# Layout.net
KiCad netlist of a schematic drawn in EasyEDA
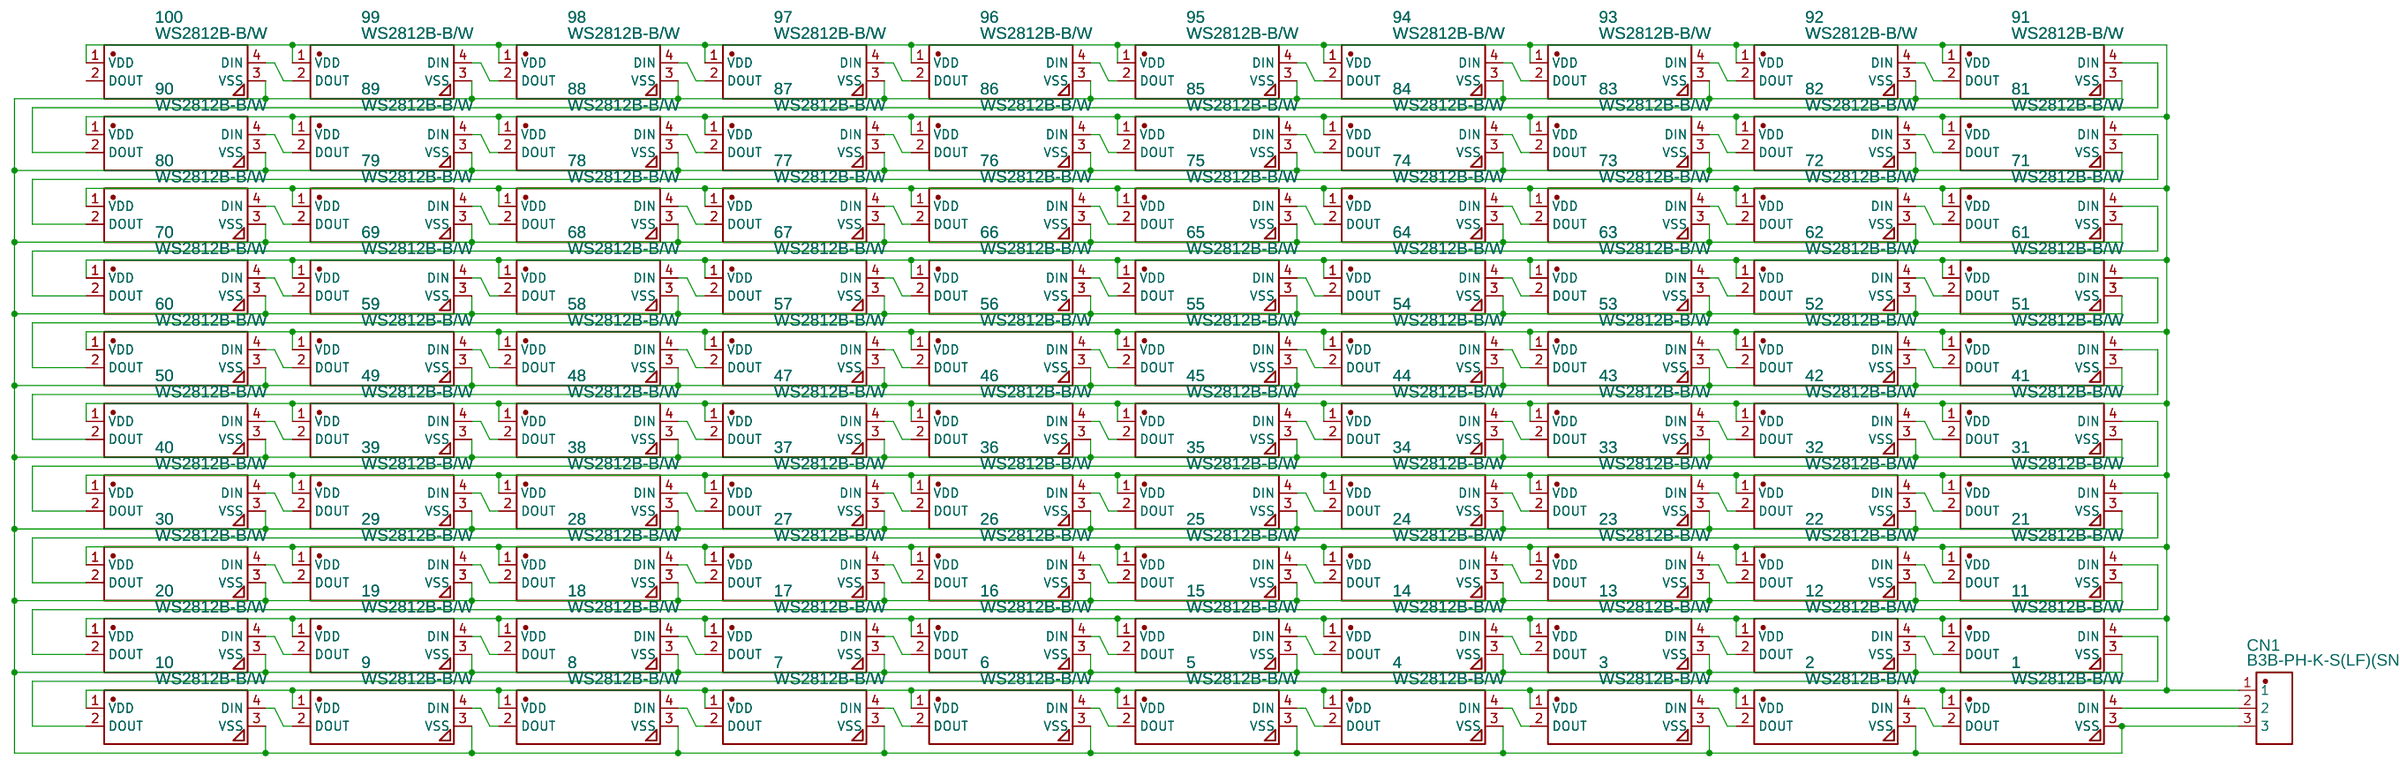
[diagram p0: schematic sheet]

(export (version "E")
  (design (tool "Eeschema 10.0.6"))
  (components
    (comp (ref "1")
      (value "WS2812B-B/W")
      (fields (field (name "Manufacturer Part") "WS2812B-B/T") (field (name "Manufacturer") "worldsemi"))
      (libsource (lib "") (part "WS2812B-B/W"))
    )
    (comp (ref "2")
      (value "WS2812B-B/W")
      (fields (field (name "Manufacturer Part") "WS2812B-B/T") (field (name "Manufacturer") "worldsemi"))
      (libsource (lib "") (part "WS2812B-B/W"))
    )
    (comp (ref "3")
      (value "WS2812B-B/W")
      (fields (field (name "Manufacturer Part") "WS2812B-B/T") (field (name "Manufacturer") "worldsemi"))
      (libsource (lib "") (part "WS2812B-B/W"))
    )
    (comp (ref "4")
      (value "WS2812B-B/W")
      (fields (field (name "Manufacturer Part") "WS2812B-B/T") (field (name "Manufacturer") "worldsemi"))
      (libsource (lib "") (part "WS2812B-B/W"))
    )
    (comp (ref "5")
      (value "WS2812B-B/W")
      (fields (field (name "Manufacturer Part") "WS2812B-B/T") (field (name "Manufacturer") "worldsemi"))
      (libsource (lib "") (part "WS2812B-B/W"))
    )
    (comp (ref "6")
      (value "WS2812B-B/W")
      (fields (field (name "Manufacturer Part") "WS2812B-B/T") (field (name "Manufacturer") "worldsemi"))
      (libsource (lib "") (part "WS2812B-B/W"))
    )
    (comp (ref "7")
      (value "WS2812B-B/W")
      (fields (field (name "Manufacturer Part") "WS2812B-B/T") (field (name "Manufacturer") "worldsemi"))
      (libsource (lib "") (part "WS2812B-B/W"))
    )
    (comp (ref "8")
      (value "WS2812B-B/W")
      (fields (field (name "Manufacturer Part") "WS2812B-B/T") (field (name "Manufacturer") "worldsemi"))
      (libsource (lib "") (part "WS2812B-B/W"))
    )
    (comp (ref "9")
      (value "WS2812B-B/W")
      (fields (field (name "Manufacturer Part") "WS2812B-B/T") (field (name "Manufacturer") "worldsemi"))
      (libsource (lib "") (part "WS2812B-B/W"))
    )
    (comp (ref "10")
      (value "WS2812B-B/W")
      (fields (field (name "Manufacturer Part") "WS2812B-B/T") (field (name "Manufacturer") "worldsemi"))
      (libsource (lib "") (part "WS2812B-B/W"))
    )
    (comp (ref "11")
      (value "WS2812B-B/W")
      (fields (field (name "Manufacturer Part") "WS2812B-B/T") (field (name "Manufacturer") "worldsemi"))
      (libsource (lib "") (part "WS2812B-B/W"))
    )
    (comp (ref "12")
      (value "WS2812B-B/W")
      (fields (field (name "Manufacturer Part") "WS2812B-B/T") (field (name "Manufacturer") "worldsemi"))
      (libsource (lib "") (part "WS2812B-B/W"))
    )
    (comp (ref "13")
      (value "WS2812B-B/W")
      (fields (field (name "Manufacturer Part") "WS2812B-B/T") (field (name "Manufacturer") "worldsemi"))
      (libsource (lib "") (part "WS2812B-B/W"))
    )
    (comp (ref "14")
      (value "WS2812B-B/W")
      (fields (field (name "Manufacturer Part") "WS2812B-B/T") (field (name "Manufacturer") "worldsemi"))
      (libsource (lib "") (part "WS2812B-B/W"))
    )
    (comp (ref "15")
      (value "WS2812B-B/W")
      (fields (field (name "Manufacturer Part") "WS2812B-B/T") (field (name "Manufacturer") "worldsemi"))
      (libsource (lib "") (part "WS2812B-B/W"))
    )
    (comp (ref "16")
      (value "WS2812B-B/W")
      (fields (field (name "Manufacturer Part") "WS2812B-B/T") (field (name "Manufacturer") "worldsemi"))
      (libsource (lib "") (part "WS2812B-B/W"))
    )
    (comp (ref "17")
      (value "WS2812B-B/W")
      (fields (field (name "Manufacturer Part") "WS2812B-B/T") (field (name "Manufacturer") "worldsemi"))
      (libsource (lib "") (part "WS2812B-B/W"))
    )
    (comp (ref "18")
      (value "WS2812B-B/W")
      (fields (field (name "Manufacturer Part") "WS2812B-B/T") (field (name "Manufacturer") "worldsemi"))
      (libsource (lib "") (part "WS2812B-B/W"))
    )
    (comp (ref "19")
      (value "WS2812B-B/W")
      (fields (field (name "Manufacturer Part") "WS2812B-B/T") (field (name "Manufacturer") "worldsemi"))
      (libsource (lib "") (part "WS2812B-B/W"))
    )
    (comp (ref "20")
      (value "WS2812B-B/W")
      (fields (field (name "Manufacturer Part") "WS2812B-B/T") (field (name "Manufacturer") "worldsemi"))
      (libsource (lib "") (part "WS2812B-B/W"))
    )
    (comp (ref "21")
      (value "WS2812B-B/W")
      (fields (field (name "Manufacturer Part") "WS2812B-B/T") (field (name "Manufacturer") "worldsemi"))
      (libsource (lib "") (part "WS2812B-B/W"))
    )
    (comp (ref "22")
      (value "WS2812B-B/W")
      (fields (field (name "Manufacturer Part") "WS2812B-B/T") (field (name "Manufacturer") "worldsemi"))
      (libsource (lib "") (part "WS2812B-B/W"))
    )
    (comp (ref "23")
      (value "WS2812B-B/W")
      (fields (field (name "Manufacturer Part") "WS2812B-B/T") (field (name "Manufacturer") "worldsemi"))
      (libsource (lib "") (part "WS2812B-B/W"))
    )
    (comp (ref "24")
      (value "WS2812B-B/W")
      (fields (field (name "Manufacturer Part") "WS2812B-B/T") (field (name "Manufacturer") "worldsemi"))
      (libsource (lib "") (part "WS2812B-B/W"))
    )
    (comp (ref "25")
      (value "WS2812B-B/W")
      (fields (field (name "Manufacturer Part") "WS2812B-B/T") (field (name "Manufacturer") "worldsemi"))
      (libsource (lib "") (part "WS2812B-B/W"))
    )
    (comp (ref "26")
      (value "WS2812B-B/W")
      (fields (field (name "Manufacturer Part") "WS2812B-B/T") (field (name "Manufacturer") "worldsemi"))
      (libsource (lib "") (part "WS2812B-B/W"))
    )
    (comp (ref "27")
      (value "WS2812B-B/W")
      (fields (field (name "Manufacturer Part") "WS2812B-B/T") (field (name "Manufacturer") "worldsemi"))
      (libsource (lib "") (part "WS2812B-B/W"))
    )
    (comp (ref "28")
      (value "WS2812B-B/W")
      (fields (field (name "Manufacturer Part") "WS2812B-B/T") (field (name "Manufacturer") "worldsemi"))
      (libsource (lib "") (part "WS2812B-B/W"))
    )
    (comp (ref "29")
      (value "WS2812B-B/W")
      (fields (field (name "Manufacturer Part") "WS2812B-B/T") (field (name "Manufacturer") "worldsemi"))
      (libsource (lib "") (part "WS2812B-B/W"))
    )
    (comp (ref "30")
      (value "WS2812B-B/W")
      (fields (field (name "Manufacturer Part") "WS2812B-B/T") (field (name "Manufacturer") "worldsemi"))
      (libsource (lib "") (part "WS2812B-B/W"))
    )
    (comp (ref "31")
      (value "WS2812B-B/W")
      (fields (field (name "Manufacturer Part") "WS2812B-B/T") (field (name "Manufacturer") "worldsemi"))
      (libsource (lib "") (part "WS2812B-B/W"))
    )
    (comp (ref "32")
      (value "WS2812B-B/W")
      (fields (field (name "Manufacturer Part") "WS2812B-B/T") (field (name "Manufacturer") "worldsemi"))
      (libsource (lib "") (part "WS2812B-B/W"))
    )
    (comp (ref "33")
      (value "WS2812B-B/W")
      (fields (field (name "Manufacturer Part") "WS2812B-B/T") (field (name "Manufacturer") "worldsemi"))
      (libsource (lib "") (part "WS2812B-B/W"))
    )
    (comp (ref "34")
      (value "WS2812B-B/W")
      (fields (field (name "Manufacturer Part") "WS2812B-B/T") (field (name "Manufacturer") "worldsemi"))
      (libsource (lib "") (part "WS2812B-B/W"))
    )
    (comp (ref "35")
      (value "WS2812B-B/W")
      (fields (field (name "Manufacturer Part") "WS2812B-B/T") (field (name "Manufacturer") "worldsemi"))
      (libsource (lib "") (part "WS2812B-B/W"))
    )
    (comp (ref "36")
      (value "WS2812B-B/W")
      (fields (field (name "Manufacturer Part") "WS2812B-B/T") (field (name "Manufacturer") "worldsemi"))
      (libsource (lib "") (part "WS2812B-B/W"))
    )
    (comp (ref "37")
      (value "WS2812B-B/W")
      (fields (field (name "Manufacturer Part") "WS2812B-B/T") (field (name "Manufacturer") "worldsemi"))
      (libsource (lib "") (part "WS2812B-B/W"))
    )
    (comp (ref "38")
      (value "WS2812B-B/W")
      (fields (field (name "Manufacturer Part") "WS2812B-B/T") (field (name "Manufacturer") "worldsemi"))
      (libsource (lib "") (part "WS2812B-B/W"))
    )
    (comp (ref "39")
      (value "WS2812B-B/W")
      (fields (field (name "Manufacturer Part") "WS2812B-B/T") (field (name "Manufacturer") "worldsemi"))
      (libsource (lib "") (part "WS2812B-B/W"))
    )
    (comp (ref "40")
      (value "WS2812B-B/W")
      (fields (field (name "Manufacturer Part") "WS2812B-B/T") (field (name "Manufacturer") "worldsemi"))
      (libsource (lib "") (part "WS2812B-B/W"))
    )
    (comp (ref "41")
      (value "WS2812B-B/W")
      (fields (field (name "Manufacturer Part") "WS2812B-B/T") (field (name "Manufacturer") "worldsemi"))
      (libsource (lib "") (part "WS2812B-B/W"))
    )
    (comp (ref "42")
      (value "WS2812B-B/W")
      (fields (field (name "Manufacturer Part") "WS2812B-B/T") (field (name "Manufacturer") "worldsemi"))
      (libsource (lib "") (part "WS2812B-B/W"))
    )
    (comp (ref "43")
      (value "WS2812B-B/W")
      (fields (field (name "Manufacturer Part") "WS2812B-B/T") (field (name "Manufacturer") "worldsemi"))
      (libsource (lib "") (part "WS2812B-B/W"))
    )
    (comp (ref "44")
      (value "WS2812B-B/W")
      (fields (field (name "Manufacturer Part") "WS2812B-B/T") (field (name "Manufacturer") "worldsemi"))
      (libsource (lib "") (part "WS2812B-B/W"))
    )
    (comp (ref "45")
      (value "WS2812B-B/W")
      (fields (field (name "Manufacturer Part") "WS2812B-B/T") (field (name "Manufacturer") "worldsemi"))
      (libsource (lib "") (part "WS2812B-B/W"))
    )
    (comp (ref "46")
      (value "WS2812B-B/W")
      (fields (field (name "Manufacturer Part") "WS2812B-B/T") (field (name "Manufacturer") "worldsemi"))
      (libsource (lib "") (part "WS2812B-B/W"))
    )
    (comp (ref "47")
      (value "WS2812B-B/W")
      (fields (field (name "Manufacturer Part") "WS2812B-B/T") (field (name "Manufacturer") "worldsemi"))
      (libsource (lib "") (part "WS2812B-B/W"))
    )
    (comp (ref "48")
      (value "WS2812B-B/W")
      (fields (field (name "Manufacturer Part") "WS2812B-B/T") (field (name "Manufacturer") "worldsemi"))
      (libsource (lib "") (part "WS2812B-B/W"))
    )
    (comp (ref "49")
      (value "WS2812B-B/W")
      (fields (field (name "Manufacturer Part") "WS2812B-B/T") (field (name "Manufacturer") "worldsemi"))
      (libsource (lib "") (part "WS2812B-B/W"))
    )
    (comp (ref "50")
      (value "WS2812B-B/W")
      (fields (field (name "Manufacturer Part") "WS2812B-B/T") (field (name "Manufacturer") "worldsemi"))
      (libsource (lib "") (part "WS2812B-B/W"))
    )
    (comp (ref "51")
      (value "WS2812B-B/W")
      (fields (field (name "Manufacturer Part") "WS2812B-B/T") (field (name "Manufacturer") "worldsemi"))
      (libsource (lib "") (part "WS2812B-B/W"))
    )
    (comp (ref "52")
      (value "WS2812B-B/W")
      (fields (field (name "Manufacturer Part") "WS2812B-B/T") (field (name "Manufacturer") "worldsemi"))
      (libsource (lib "") (part "WS2812B-B/W"))
    )
    (comp (ref "53")
      (value "WS2812B-B/W")
      (fields (field (name "Manufacturer Part") "WS2812B-B/T") (field (name "Manufacturer") "worldsemi"))
      (libsource (lib "") (part "WS2812B-B/W"))
    )
    (comp (ref "54")
      (value "WS2812B-B/W")
      (fields (field (name "Manufacturer Part") "WS2812B-B/T") (field (name "Manufacturer") "worldsemi"))
      (libsource (lib "") (part "WS2812B-B/W"))
    )
    (comp (ref "55")
      (value "WS2812B-B/W")
      (fields (field (name "Manufacturer Part") "WS2812B-B/T") (field (name "Manufacturer") "worldsemi"))
      (libsource (lib "") (part "WS2812B-B/W"))
    )
    (comp (ref "56")
      (value "WS2812B-B/W")
      (fields (field (name "Manufacturer Part") "WS2812B-B/T") (field (name "Manufacturer") "worldsemi"))
      (libsource (lib "") (part "WS2812B-B/W"))
    )
    (comp (ref "57")
      (value "WS2812B-B/W")
      (fields (field (name "Manufacturer Part") "WS2812B-B/T") (field (name "Manufacturer") "worldsemi"))
      (libsource (lib "") (part "WS2812B-B/W"))
    )
    (comp (ref "58")
      (value "WS2812B-B/W")
      (fields (field (name "Manufacturer Part") "WS2812B-B/T") (field (name "Manufacturer") "worldsemi"))
      (libsource (lib "") (part "WS2812B-B/W"))
    )
    (comp (ref "59")
      (value "WS2812B-B/W")
      (fields (field (name "Manufacturer Part") "WS2812B-B/T") (field (name "Manufacturer") "worldsemi"))
      (libsource (lib "") (part "WS2812B-B/W"))
    )
    (comp (ref "60")
      (value "WS2812B-B/W")
      (fields (field (name "Manufacturer Part") "WS2812B-B/T") (field (name "Manufacturer") "worldsemi"))
      (libsource (lib "") (part "WS2812B-B/W"))
    )
    (comp (ref "61")
      (value "WS2812B-B/W")
      (fields (field (name "Manufacturer Part") "WS2812B-B/T") (field (name "Manufacturer") "worldsemi"))
      (libsource (lib "") (part "WS2812B-B/W"))
    )
    (comp (ref "62")
      (value "WS2812B-B/W")
      (fields (field (name "Manufacturer Part") "WS2812B-B/T") (field (name "Manufacturer") "worldsemi"))
      (libsource (lib "") (part "WS2812B-B/W"))
    )
    (comp (ref "63")
      (value "WS2812B-B/W")
      (fields (field (name "Manufacturer Part") "WS2812B-B/T") (field (name "Manufacturer") "worldsemi"))
      (libsource (lib "") (part "WS2812B-B/W"))
    )
    (comp (ref "64")
      (value "WS2812B-B/W")
      (fields (field (name "Manufacturer Part") "WS2812B-B/T") (field (name "Manufacturer") "worldsemi"))
      (libsource (lib "") (part "WS2812B-B/W"))
    )
    (comp (ref "65")
      (value "WS2812B-B/W")
      (fields (field (name "Manufacturer Part") "WS2812B-B/T") (field (name "Manufacturer") "worldsemi"))
      (libsource (lib "") (part "WS2812B-B/W"))
    )
    (comp (ref "66")
      (value "WS2812B-B/W")
      (fields (field (name "Manufacturer Part") "WS2812B-B/T") (field (name "Manufacturer") "worldsemi"))
      (libsource (lib "") (part "WS2812B-B/W"))
    )
    (comp (ref "67")
      (value "WS2812B-B/W")
      (fields (field (name "Manufacturer Part") "WS2812B-B/T") (field (name "Manufacturer") "worldsemi"))
      (libsource (lib "") (part "WS2812B-B/W"))
    )
    (comp (ref "68")
      (value "WS2812B-B/W")
      (fields (field (name "Manufacturer Part") "WS2812B-B/T") (field (name "Manufacturer") "worldsemi"))
      (libsource (lib "") (part "WS2812B-B/W"))
    )
    (comp (ref "69")
      (value "WS2812B-B/W")
      (fields (field (name "Manufacturer Part") "WS2812B-B/T") (field (name "Manufacturer") "worldsemi"))
      (libsource (lib "") (part "WS2812B-B/W"))
    )
    (comp (ref "70")
      (value "WS2812B-B/W")
      (fields (field (name "Manufacturer Part") "WS2812B-B/T") (field (name "Manufacturer") "worldsemi"))
      (libsource (lib "") (part "WS2812B-B/W"))
    )
    (comp (ref "71")
      (value "WS2812B-B/W")
      (fields (field (name "Manufacturer Part") "WS2812B-B/T") (field (name "Manufacturer") "worldsemi"))
      (libsource (lib "") (part "WS2812B-B/W"))
    )
    (comp (ref "72")
      (value "WS2812B-B/W")
      (fields (field (name "Manufacturer Part") "WS2812B-B/T") (field (name "Manufacturer") "worldsemi"))
      (libsource (lib "") (part "WS2812B-B/W"))
    )
    (comp (ref "73")
      (value "WS2812B-B/W")
      (fields (field (name "Manufacturer Part") "WS2812B-B/T") (field (name "Manufacturer") "worldsemi"))
      (libsource (lib "") (part "WS2812B-B/W"))
    )
    (comp (ref "74")
      (value "WS2812B-B/W")
      (fields (field (name "Manufacturer Part") "WS2812B-B/T") (field (name "Manufacturer") "worldsemi"))
      (libsource (lib "") (part "WS2812B-B/W"))
    )
    (comp (ref "75")
      (value "WS2812B-B/W")
      (fields (field (name "Manufacturer Part") "WS2812B-B/T") (field (name "Manufacturer") "worldsemi"))
      (libsource (lib "") (part "WS2812B-B/W"))
    )
    (comp (ref "76")
      (value "WS2812B-B/W")
      (fields (field (name "Manufacturer Part") "WS2812B-B/T") (field (name "Manufacturer") "worldsemi"))
      (libsource (lib "") (part "WS2812B-B/W"))
    )
    (comp (ref "77")
      (value "WS2812B-B/W")
      (fields (field (name "Manufacturer Part") "WS2812B-B/T") (field (name "Manufacturer") "worldsemi"))
      (libsource (lib "") (part "WS2812B-B/W"))
    )
    (comp (ref "78")
      (value "WS2812B-B/W")
      (fields (field (name "Manufacturer Part") "WS2812B-B/T") (field (name "Manufacturer") "worldsemi"))
      (libsource (lib "") (part "WS2812B-B/W"))
    )
    (comp (ref "79")
      (value "WS2812B-B/W")
      (fields (field (name "Manufacturer Part") "WS2812B-B/T") (field (name "Manufacturer") "worldsemi"))
      (libsource (lib "") (part "WS2812B-B/W"))
    )
    (comp (ref "80")
      (value "WS2812B-B/W")
      (fields (field (name "Manufacturer Part") "WS2812B-B/T") (field (name "Manufacturer") "worldsemi"))
      (libsource (lib "") (part "WS2812B-B/W"))
    )
    (comp (ref "81")
      (value "WS2812B-B/W")
      (fields (field (name "Manufacturer Part") "WS2812B-B/T") (field (name "Manufacturer") "worldsemi"))
      (libsource (lib "") (part "WS2812B-B/W"))
    )
    (comp (ref "82")
      (value "WS2812B-B/W")
      (fields (field (name "Manufacturer Part") "WS2812B-B/T") (field (name "Manufacturer") "worldsemi"))
      (libsource (lib "") (part "WS2812B-B/W"))
    )
    (comp (ref "83")
      (value "WS2812B-B/W")
      (fields (field (name "Manufacturer Part") "WS2812B-B/T") (field (name "Manufacturer") "worldsemi"))
      (libsource (lib "") (part "WS2812B-B/W"))
    )
    (comp (ref "84")
      (value "WS2812B-B/W")
      (fields (field (name "Manufacturer Part") "WS2812B-B/T") (field (name "Manufacturer") "worldsemi"))
      (libsource (lib "") (part "WS2812B-B/W"))
    )
    (comp (ref "85")
      (value "WS2812B-B/W")
      (fields (field (name "Manufacturer Part") "WS2812B-B/T") (field (name "Manufacturer") "worldsemi"))
      (libsource (lib "") (part "WS2812B-B/W"))
    )
    (comp (ref "86")
      (value "WS2812B-B/W")
      (fields (field (name "Manufacturer Part") "WS2812B-B/T") (field (name "Manufacturer") "worldsemi"))
      (libsource (lib "") (part "WS2812B-B/W"))
    )
    (comp (ref "87")
      (value "WS2812B-B/W")
      (fields (field (name "Manufacturer Part") "WS2812B-B/T") (field (name "Manufacturer") "worldsemi"))
      (libsource (lib "") (part "WS2812B-B/W"))
    )
    (comp (ref "88")
      (value "WS2812B-B/W")
      (fields (field (name "Manufacturer Part") "WS2812B-B/T") (field (name "Manufacturer") "worldsemi"))
      (libsource (lib "") (part "WS2812B-B/W"))
    )
    (comp (ref "89")
      (value "WS2812B-B/W")
      (fields (field (name "Manufacturer Part") "WS2812B-B/T") (field (name "Manufacturer") "worldsemi"))
      (libsource (lib "") (part "WS2812B-B/W"))
    )
    (comp (ref "90")
      (value "WS2812B-B/W")
      (fields (field (name "Manufacturer Part") "WS2812B-B/T") (field (name "Manufacturer") "worldsemi"))
      (libsource (lib "") (part "WS2812B-B/W"))
    )
    (comp (ref "91")
      (value "WS2812B-B/W")
      (fields (field (name "Manufacturer Part") "WS2812B-B/T") (field (name "Manufacturer") "worldsemi"))
      (libsource (lib "") (part "WS2812B-B/W"))
    )
    (comp (ref "92")
      (value "WS2812B-B/W")
      (fields (field (name "Manufacturer Part") "WS2812B-B/T") (field (name "Manufacturer") "worldsemi"))
      (libsource (lib "") (part "WS2812B-B/W"))
    )
    (comp (ref "93")
      (value "WS2812B-B/W")
      (fields (field (name "Manufacturer Part") "WS2812B-B/T") (field (name "Manufacturer") "worldsemi"))
      (libsource (lib "") (part "WS2812B-B/W"))
    )
    (comp (ref "94")
      (value "WS2812B-B/W")
      (fields (field (name "Manufacturer Part") "WS2812B-B/T") (field (name "Manufacturer") "worldsemi"))
      (libsource (lib "") (part "WS2812B-B/W"))
    )
    (comp (ref "95")
      (value "WS2812B-B/W")
      (fields (field (name "Manufacturer Part") "WS2812B-B/T") (field (name "Manufacturer") "worldsemi"))
      (libsource (lib "") (part "WS2812B-B/W"))
    )
    (comp (ref "96")
      (value "WS2812B-B/W")
      (fields (field (name "Manufacturer Part") "WS2812B-B/T") (field (name "Manufacturer") "worldsemi"))
      (libsource (lib "") (part "WS2812B-B/W"))
    )
    (comp (ref "97")
      (value "WS2812B-B/W")
      (fields (field (name "Manufacturer Part") "WS2812B-B/T") (field (name "Manufacturer") "worldsemi"))
      (libsource (lib "") (part "WS2812B-B/W"))
    )
    (comp (ref "98")
      (value "WS2812B-B/W")
      (fields (field (name "Manufacturer Part") "WS2812B-B/T") (field (name "Manufacturer") "worldsemi"))
      (libsource (lib "") (part "WS2812B-B/W"))
    )
    (comp (ref "99")
      (value "WS2812B-B/W")
      (fields (field (name "Manufacturer Part") "WS2812B-B/T") (field (name "Manufacturer") "worldsemi"))
      (libsource (lib "") (part "WS2812B-B/W"))
    )
    (comp (ref "100")
      (value "WS2812B-B/W")
      (fields (field (name "Manufacturer Part") "WS2812B-B/T") (field (name "Manufacturer") "worldsemi"))
      (libsource (lib "") (part "WS2812B-B/W"))
    )
    (comp (ref "CN1")
      (value "B3B-PH-K-S(LF)(SN)")
      (fields (field (name "Manufacturer") "JST"))
      (libsource (lib "") (part "B3B-PH-K-S(LF)(SN)"))
    )
  )
  (nets
    (net (code "1") (name "Net-(1-DIN)") (class "Default")
      (node (ref "1") (pin "4") (pinfunction "DIN_4") (pintype "unspecified"))
      (node (ref "CN1") (pin "2") (pinfunction "2_2") (pintype "unspecified"))
    )
    (net (code "2") (name "Net-(1-DOUT)") (class "Default")
      (node (ref "1") (pin "2") (pinfunction "DOUT_2") (pintype "unspecified"))
      (node (ref "2") (pin "4") (pinfunction "DIN_4") (pintype "unspecified"))
    )
    (net (code "3") (name "Net-(1-VDD)") (class "Default")
      (node (ref "1") (pin "1") (pinfunction "VDD_1") (pintype "unspecified"))
      (node (ref "10") (pin "1") (pinfunction "VDD_1") (pintype "unspecified"))
      (node (ref "100") (pin "1") (pinfunction "VDD_1") (pintype "unspecified"))
      (node (ref "11") (pin "1") (pinfunction "VDD_1") (pintype "unspecified"))
      (node (ref "12") (pin "1") (pinfunction "VDD_1") (pintype "unspecified"))
      (node (ref "13") (pin "1") (pinfunction "VDD_1") (pintype "unspecified"))
      (node (ref "14") (pin "1") (pinfunction "VDD_1") (pintype "unspecified"))
      (node (ref "15") (pin "1") (pinfunction "VDD_1") (pintype "unspecified"))
      (node (ref "16") (pin "1") (pinfunction "VDD_1") (pintype "unspecified"))
      (node (ref "17") (pin "1") (pinfunction "VDD_1") (pintype "unspecified"))
      (node (ref "18") (pin "1") (pinfunction "VDD_1") (pintype "unspecified"))
      (node (ref "19") (pin "1") (pinfunction "VDD_1") (pintype "unspecified"))
      (node (ref "2") (pin "1") (pinfunction "VDD_1") (pintype "unspecified"))
      (node (ref "20") (pin "1") (pinfunction "VDD_1") (pintype "unspecified"))
      (node (ref "21") (pin "1") (pinfunction "VDD_1") (pintype "unspecified"))
      (node (ref "22") (pin "1") (pinfunction "VDD_1") (pintype "unspecified"))
      (node (ref "23") (pin "1") (pinfunction "VDD_1") (pintype "unspecified"))
      (node (ref "24") (pin "1") (pinfunction "VDD_1") (pintype "unspecified"))
      (node (ref "25") (pin "1") (pinfunction "VDD_1") (pintype "unspecified"))
      (node (ref "26") (pin "1") (pinfunction "VDD_1") (pintype "unspecified"))
      (node (ref "27") (pin "1") (pinfunction "VDD_1") (pintype "unspecified"))
      (node (ref "28") (pin "1") (pinfunction "VDD_1") (pintype "unspecified"))
      (node (ref "29") (pin "1") (pinfunction "VDD_1") (pintype "unspecified"))
      (node (ref "3") (pin "1") (pinfunction "VDD_1") (pintype "unspecified"))
      (node (ref "30") (pin "1") (pinfunction "VDD_1") (pintype "unspecified"))
      (node (ref "31") (pin "1") (pinfunction "VDD_1") (pintype "unspecified"))
      (node (ref "32") (pin "1") (pinfunction "VDD_1") (pintype "unspecified"))
      (node (ref "33") (pin "1") (pinfunction "VDD_1") (pintype "unspecified"))
      (node (ref "34") (pin "1") (pinfunction "VDD_1") (pintype "unspecified"))
      (node (ref "35") (pin "1") (pinfunction "VDD_1") (pintype "unspecified"))
      (node (ref "36") (pin "1") (pinfunction "VDD_1") (pintype "unspecified"))
      (node (ref "37") (pin "1") (pinfunction "VDD_1") (pintype "unspecified"))
      (node (ref "38") (pin "1") (pinfunction "VDD_1") (pintype "unspecified"))
      (node (ref "39") (pin "1") (pinfunction "VDD_1") (pintype "unspecified"))
      (node (ref "4") (pin "1") (pinfunction "VDD_1") (pintype "unspecified"))
      (node (ref "40") (pin "1") (pinfunction "VDD_1") (pintype "unspecified"))
      (node (ref "41") (pin "1") (pinfunction "VDD_1") (pintype "unspecified"))
      (node (ref "42") (pin "1") (pinfunction "VDD_1") (pintype "unspecified"))
      (node (ref "43") (pin "1") (pinfunction "VDD_1") (pintype "unspecified"))
      (node (ref "44") (pin "1") (pinfunction "VDD_1") (pintype "unspecified"))
      (node (ref "45") (pin "1") (pinfunction "VDD_1") (pintype "unspecified"))
      (node (ref "46") (pin "1") (pinfunction "VDD_1") (pintype "unspecified"))
      (node (ref "47") (pin "1") (pinfunction "VDD_1") (pintype "unspecified"))
      (node (ref "48") (pin "1") (pinfunction "VDD_1") (pintype "unspecified"))
      (node (ref "49") (pin "1") (pinfunction "VDD_1") (pintype "unspecified"))
      (node (ref "5") (pin "1") (pinfunction "VDD_1") (pintype "unspecified"))
      (node (ref "50") (pin "1") (pinfunction "VDD_1") (pintype "unspecified"))
      (node (ref "51") (pin "1") (pinfunction "VDD_1") (pintype "unspecified"))
      (node (ref "52") (pin "1") (pinfunction "VDD_1") (pintype "unspecified"))
      (node (ref "53") (pin "1") (pinfunction "VDD_1") (pintype "unspecified"))
      (node (ref "54") (pin "1") (pinfunction "VDD_1") (pintype "unspecified"))
      (node (ref "55") (pin "1") (pinfunction "VDD_1") (pintype "unspecified"))
      (node (ref "56") (pin "1") (pinfunction "VDD_1") (pintype "unspecified"))
      (node (ref "57") (pin "1") (pinfunction "VDD_1") (pintype "unspecified"))
      (node (ref "58") (pin "1") (pinfunction "VDD_1") (pintype "unspecified"))
      (node (ref "59") (pin "1") (pinfunction "VDD_1") (pintype "unspecified"))
      (node (ref "6") (pin "1") (pinfunction "VDD_1") (pintype "unspecified"))
      (node (ref "60") (pin "1") (pinfunction "VDD_1") (pintype "unspecified"))
      (node (ref "61") (pin "1") (pinfunction "VDD_1") (pintype "unspecified"))
      (node (ref "62") (pin "1") (pinfunction "VDD_1") (pintype "unspecified"))
      (node (ref "63") (pin "1") (pinfunction "VDD_1") (pintype "unspecified"))
      (node (ref "64") (pin "1") (pinfunction "VDD_1") (pintype "unspecified"))
      (node (ref "65") (pin "1") (pinfunction "VDD_1") (pintype "unspecified"))
      (node (ref "66") (pin "1") (pinfunction "VDD_1") (pintype "unspecified"))
      (node (ref "67") (pin "1") (pinfunction "VDD_1") (pintype "unspecified"))
      (node (ref "68") (pin "1") (pinfunction "VDD_1") (pintype "unspecified"))
      (node (ref "69") (pin "1") (pinfunction "VDD_1") (pintype "unspecified"))
      (node (ref "7") (pin "1") (pinfunction "VDD_1") (pintype "unspecified"))
      (node (ref "70") (pin "1") (pinfunction "VDD_1") (pintype "unspecified"))
      (node (ref "71") (pin "1") (pinfunction "VDD_1") (pintype "unspecified"))
      (node (ref "72") (pin "1") (pinfunction "VDD_1") (pintype "unspecified"))
      (node (ref "73") (pin "1") (pinfunction "VDD_1") (pintype "unspecified"))
      (node (ref "74") (pin "1") (pinfunction "VDD_1") (pintype "unspecified"))
      (node (ref "75") (pin "1") (pinfunction "VDD_1") (pintype "unspecified"))
      (node (ref "76") (pin "1") (pinfunction "VDD_1") (pintype "unspecified"))
      (node (ref "77") (pin "1") (pinfunction "VDD_1") (pintype "unspecified"))
      (node (ref "78") (pin "1") (pinfunction "VDD_1") (pintype "unspecified"))
      (node (ref "79") (pin "1") (pinfunction "VDD_1") (pintype "unspecified"))
      (node (ref "8") (pin "1") (pinfunction "VDD_1") (pintype "unspecified"))
      (node (ref "80") (pin "1") (pinfunction "VDD_1") (pintype "unspecified"))
      (node (ref "81") (pin "1") (pinfunction "VDD_1") (pintype "unspecified"))
      (node (ref "82") (pin "1") (pinfunction "VDD_1") (pintype "unspecified"))
      (node (ref "83") (pin "1") (pinfunction "VDD_1") (pintype "unspecified"))
      (node (ref "84") (pin "1") (pinfunction "VDD_1") (pintype "unspecified"))
      (node (ref "85") (pin "1") (pinfunction "VDD_1") (pintype "unspecified"))
      (node (ref "86") (pin "1") (pinfunction "VDD_1") (pintype "unspecified"))
      (node (ref "87") (pin "1") (pinfunction "VDD_1") (pintype "unspecified"))
      (node (ref "88") (pin "1") (pinfunction "VDD_1") (pintype "unspecified"))
      (node (ref "89") (pin "1") (pinfunction "VDD_1") (pintype "unspecified"))
      (node (ref "9") (pin "1") (pinfunction "VDD_1") (pintype "unspecified"))
      (node (ref "90") (pin "1") (pinfunction "VDD_1") (pintype "unspecified"))
      (node (ref "91") (pin "1") (pinfunction "VDD_1") (pintype "unspecified"))
      (node (ref "92") (pin "1") (pinfunction "VDD_1") (pintype "unspecified"))
      (node (ref "93") (pin "1") (pinfunction "VDD_1") (pintype "unspecified"))
      (node (ref "94") (pin "1") (pinfunction "VDD_1") (pintype "unspecified"))
      (node (ref "95") (pin "1") (pinfunction "VDD_1") (pintype "unspecified"))
      (node (ref "96") (pin "1") (pinfunction "VDD_1") (pintype "unspecified"))
      (node (ref "97") (pin "1") (pinfunction "VDD_1") (pintype "unspecified"))
      (node (ref "98") (pin "1") (pinfunction "VDD_1") (pintype "unspecified"))
      (node (ref "99") (pin "1") (pinfunction "VDD_1") (pintype "unspecified"))
      (node (ref "CN1") (pin "1") (pinfunction "1_1") (pintype "unspecified"))
    )
    (net (code "4") (name "Net-(1-VSS)") (class "Default")
      (node (ref "1") (pin "3") (pinfunction "VSS_3") (pintype "unspecified"))
      (node (ref "10") (pin "3") (pinfunction "VSS_3") (pintype "unspecified"))
      (node (ref "100") (pin "3") (pinfunction "VSS_3") (pintype "unspecified"))
      (node (ref "11") (pin "3") (pinfunction "VSS_3") (pintype "unspecified"))
      (node (ref "12") (pin "3") (pinfunction "VSS_3") (pintype "unspecified"))
      (node (ref "13") (pin "3") (pinfunction "VSS_3") (pintype "unspecified"))
      (node (ref "14") (pin "3") (pinfunction "VSS_3") (pintype "unspecified"))
      (node (ref "15") (pin "3") (pinfunction "VSS_3") (pintype "unspecified"))
      (node (ref "16") (pin "3") (pinfunction "VSS_3") (pintype "unspecified"))
      (node (ref "17") (pin "3") (pinfunction "VSS_3") (pintype "unspecified"))
      (node (ref "18") (pin "3") (pinfunction "VSS_3") (pintype "unspecified"))
      (node (ref "19") (pin "3") (pinfunction "VSS_3") (pintype "unspecified"))
      (node (ref "2") (pin "3") (pinfunction "VSS_3") (pintype "unspecified"))
      (node (ref "20") (pin "3") (pinfunction "VSS_3") (pintype "unspecified"))
      (node (ref "21") (pin "3") (pinfunction "VSS_3") (pintype "unspecified"))
      (node (ref "22") (pin "3") (pinfunction "VSS_3") (pintype "unspecified"))
      (node (ref "23") (pin "3") (pinfunction "VSS_3") (pintype "unspecified"))
      (node (ref "24") (pin "3") (pinfunction "VSS_3") (pintype "unspecified"))
      (node (ref "25") (pin "3") (pinfunction "VSS_3") (pintype "unspecified"))
      (node (ref "26") (pin "3") (pinfunction "VSS_3") (pintype "unspecified"))
      (node (ref "27") (pin "3") (pinfunction "VSS_3") (pintype "unspecified"))
      (node (ref "28") (pin "3") (pinfunction "VSS_3") (pintype "unspecified"))
      (node (ref "29") (pin "3") (pinfunction "VSS_3") (pintype "unspecified"))
      (node (ref "3") (pin "3") (pinfunction "VSS_3") (pintype "unspecified"))
      (node (ref "30") (pin "3") (pinfunction "VSS_3") (pintype "unspecified"))
      (node (ref "31") (pin "3") (pinfunction "VSS_3") (pintype "unspecified"))
      (node (ref "32") (pin "3") (pinfunction "VSS_3") (pintype "unspecified"))
      (node (ref "33") (pin "3") (pinfunction "VSS_3") (pintype "unspecified"))
      (node (ref "34") (pin "3") (pinfunction "VSS_3") (pintype "unspecified"))
      (node (ref "35") (pin "3") (pinfunction "VSS_3") (pintype "unspecified"))
      (node (ref "36") (pin "3") (pinfunction "VSS_3") (pintype "unspecified"))
      (node (ref "37") (pin "3") (pinfunction "VSS_3") (pintype "unspecified"))
      (node (ref "38") (pin "3") (pinfunction "VSS_3") (pintype "unspecified"))
      (node (ref "39") (pin "3") (pinfunction "VSS_3") (pintype "unspecified"))
      (node (ref "4") (pin "3") (pinfunction "VSS_3") (pintype "unspecified"))
      (node (ref "40") (pin "3") (pinfunction "VSS_3") (pintype "unspecified"))
      (node (ref "41") (pin "3") (pinfunction "VSS_3") (pintype "unspecified"))
      (node (ref "42") (pin "3") (pinfunction "VSS_3") (pintype "unspecified"))
      (node (ref "43") (pin "3") (pinfunction "VSS_3") (pintype "unspecified"))
      (node (ref "44") (pin "3") (pinfunction "VSS_3") (pintype "unspecified"))
      (node (ref "45") (pin "3") (pinfunction "VSS_3") (pintype "unspecified"))
      (node (ref "46") (pin "3") (pinfunction "VSS_3") (pintype "unspecified"))
      (node (ref "47") (pin "3") (pinfunction "VSS_3") (pintype "unspecified"))
      (node (ref "48") (pin "3") (pinfunction "VSS_3") (pintype "unspecified"))
      (node (ref "49") (pin "3") (pinfunction "VSS_3") (pintype "unspecified"))
      (node (ref "5") (pin "3") (pinfunction "VSS_3") (pintype "unspecified"))
      (node (ref "50") (pin "3") (pinfunction "VSS_3") (pintype "unspecified"))
      (node (ref "51") (pin "3") (pinfunction "VSS_3") (pintype "unspecified"))
      (node (ref "52") (pin "3") (pinfunction "VSS_3") (pintype "unspecified"))
      (node (ref "53") (pin "3") (pinfunction "VSS_3") (pintype "unspecified"))
      (node (ref "54") (pin "3") (pinfunction "VSS_3") (pintype "unspecified"))
      (node (ref "55") (pin "3") (pinfunction "VSS_3") (pintype "unspecified"))
      (node (ref "56") (pin "3") (pinfunction "VSS_3") (pintype "unspecified"))
      (node (ref "57") (pin "3") (pinfunction "VSS_3") (pintype "unspecified"))
      (node (ref "58") (pin "3") (pinfunction "VSS_3") (pintype "unspecified"))
      (node (ref "59") (pin "3") (pinfunction "VSS_3") (pintype "unspecified"))
      (node (ref "6") (pin "3") (pinfunction "VSS_3") (pintype "unspecified"))
      (node (ref "60") (pin "3") (pinfunction "VSS_3") (pintype "unspecified"))
      (node (ref "61") (pin "3") (pinfunction "VSS_3") (pintype "unspecified"))
      (node (ref "62") (pin "3") (pinfunction "VSS_3") (pintype "unspecified"))
      (node (ref "63") (pin "3") (pinfunction "VSS_3") (pintype "unspecified"))
      (node (ref "64") (pin "3") (pinfunction "VSS_3") (pintype "unspecified"))
      (node (ref "65") (pin "3") (pinfunction "VSS_3") (pintype "unspecified"))
      (node (ref "66") (pin "3") (pinfunction "VSS_3") (pintype "unspecified"))
      (node (ref "67") (pin "3") (pinfunction "VSS_3") (pintype "unspecified"))
      (node (ref "68") (pin "3") (pinfunction "VSS_3") (pintype "unspecified"))
      (node (ref "69") (pin "3") (pinfunction "VSS_3") (pintype "unspecified"))
      (node (ref "7") (pin "3") (pinfunction "VSS_3") (pintype "unspecified"))
      (node (ref "70") (pin "3") (pinfunction "VSS_3") (pintype "unspecified"))
      (node (ref "71") (pin "3") (pinfunction "VSS_3") (pintype "unspecified"))
      (node (ref "72") (pin "3") (pinfunction "VSS_3") (pintype "unspecified"))
      (node (ref "73") (pin "3") (pinfunction "VSS_3") (pintype "unspecified"))
      (node (ref "74") (pin "3") (pinfunction "VSS_3") (pintype "unspecified"))
      (node (ref "75") (pin "3") (pinfunction "VSS_3") (pintype "unspecified"))
      (node (ref "76") (pin "3") (pinfunction "VSS_3") (pintype "unspecified"))
      (node (ref "77") (pin "3") (pinfunction "VSS_3") (pintype "unspecified"))
      (node (ref "78") (pin "3") (pinfunction "VSS_3") (pintype "unspecified"))
      (node (ref "79") (pin "3") (pinfunction "VSS_3") (pintype "unspecified"))
      (node (ref "8") (pin "3") (pinfunction "VSS_3") (pintype "unspecified"))
      (node (ref "80") (pin "3") (pinfunction "VSS_3") (pintype "unspecified"))
      (node (ref "81") (pin "3") (pinfunction "VSS_3") (pintype "unspecified"))
      (node (ref "82") (pin "3") (pinfunction "VSS_3") (pintype "unspecified"))
      (node (ref "83") (pin "3") (pinfunction "VSS_3") (pintype "unspecified"))
      (node (ref "84") (pin "3") (pinfunction "VSS_3") (pintype "unspecified"))
      (node (ref "85") (pin "3") (pinfunction "VSS_3") (pintype "unspecified"))
      (node (ref "86") (pin "3") (pinfunction "VSS_3") (pintype "unspecified"))
      (node (ref "87") (pin "3") (pinfunction "VSS_3") (pintype "unspecified"))
      (node (ref "88") (pin "3") (pinfunction "VSS_3") (pintype "unspecified"))
      (node (ref "89") (pin "3") (pinfunction "VSS_3") (pintype "unspecified"))
      (node (ref "9") (pin "3") (pinfunction "VSS_3") (pintype "unspecified"))
      (node (ref "90") (pin "3") (pinfunction "VSS_3") (pintype "unspecified"))
      (node (ref "91") (pin "3") (pinfunction "VSS_3") (pintype "unspecified"))
      (node (ref "92") (pin "3") (pinfunction "VSS_3") (pintype "unspecified"))
      (node (ref "93") (pin "3") (pinfunction "VSS_3") (pintype "unspecified"))
      (node (ref "94") (pin "3") (pinfunction "VSS_3") (pintype "unspecified"))
      (node (ref "95") (pin "3") (pinfunction "VSS_3") (pintype "unspecified"))
      (node (ref "96") (pin "3") (pinfunction "VSS_3") (pintype "unspecified"))
      (node (ref "97") (pin "3") (pinfunction "VSS_3") (pintype "unspecified"))
      (node (ref "98") (pin "3") (pinfunction "VSS_3") (pintype "unspecified"))
      (node (ref "99") (pin "3") (pinfunction "VSS_3") (pintype "unspecified"))
      (node (ref "CN1") (pin "3") (pinfunction "3_3") (pintype "unspecified"))
    )
    (net (code "5") (name "Net-(2-DOUT)") (class "Default")
      (node (ref "2") (pin "2") (pinfunction "DOUT_2") (pintype "unspecified"))
      (node (ref "3") (pin "4") (pinfunction "DIN_4") (pintype "unspecified"))
    )
    (net (code "6") (name "Net-(3-DOUT)") (class "Default")
      (node (ref "3") (pin "2") (pinfunction "DOUT_2") (pintype "unspecified"))
      (node (ref "4") (pin "4") (pinfunction "DIN_4") (pintype "unspecified"))
    )
    (net (code "7") (name "Net-(4-DOUT)") (class "Default")
      (node (ref "4") (pin "2") (pinfunction "DOUT_2") (pintype "unspecified"))
      (node (ref "5") (pin "4") (pinfunction "DIN_4") (pintype "unspecified"))
    )
    (net (code "8") (name "Net-(5-DOUT)") (class "Default")
      (node (ref "5") (pin "2") (pinfunction "DOUT_2") (pintype "unspecified"))
      (node (ref "6") (pin "4") (pinfunction "DIN_4") (pintype "unspecified"))
    )
    (net (code "9") (name "Net-(6-DOUT)") (class "Default")
      (node (ref "6") (pin "2") (pinfunction "DOUT_2") (pintype "unspecified"))
      (node (ref "7") (pin "4") (pinfunction "DIN_4") (pintype "unspecified"))
    )
    (net (code "10") (name "Net-(7-DOUT)") (class "Default")
      (node (ref "7") (pin "2") (pinfunction "DOUT_2") (pintype "unspecified"))
      (node (ref "8") (pin "4") (pinfunction "DIN_4") (pintype "unspecified"))
    )
    (net (code "11") (name "Net-(8-DOUT)") (class "Default")
      (node (ref "8") (pin "2") (pinfunction "DOUT_2") (pintype "unspecified"))
      (node (ref "9") (pin "4") (pinfunction "DIN_4") (pintype "unspecified"))
    )
    (net (code "12") (name "Net-(10-DIN)") (class "Default")
      (node (ref "10") (pin "4") (pinfunction "DIN_4") (pintype "unspecified"))
      (node (ref "9") (pin "2") (pinfunction "DOUT_2") (pintype "unspecified"))
    )
    (net (code "13") (name "Net-(10-DOUT)") (class "Default")
      (node (ref "10") (pin "2") (pinfunction "DOUT_2") (pintype "unspecified"))
      (node (ref "11") (pin "4") (pinfunction "DIN_4") (pintype "unspecified"))
    )
    (net (code "14") (name "Net-(11-DOUT)") (class "Default")
      (node (ref "11") (pin "2") (pinfunction "DOUT_2") (pintype "unspecified"))
      (node (ref "12") (pin "4") (pinfunction "DIN_4") (pintype "unspecified"))
    )
    (net (code "15") (name "Net-(12-DOUT)") (class "Default")
      (node (ref "12") (pin "2") (pinfunction "DOUT_2") (pintype "unspecified"))
      (node (ref "13") (pin "4") (pinfunction "DIN_4") (pintype "unspecified"))
    )
    (net (code "16") (name "Net-(13-DOUT)") (class "Default")
      (node (ref "13") (pin "2") (pinfunction "DOUT_2") (pintype "unspecified"))
      (node (ref "14") (pin "4") (pinfunction "DIN_4") (pintype "unspecified"))
    )
    (net (code "17") (name "Net-(14-DOUT)") (class "Default")
      (node (ref "14") (pin "2") (pinfunction "DOUT_2") (pintype "unspecified"))
      (node (ref "15") (pin "4") (pinfunction "DIN_4") (pintype "unspecified"))
    )
    (net (code "18") (name "Net-(15-DOUT)") (class "Default")
      (node (ref "15") (pin "2") (pinfunction "DOUT_2") (pintype "unspecified"))
      (node (ref "16") (pin "4") (pinfunction "DIN_4") (pintype "unspecified"))
    )
    (net (code "19") (name "Net-(16-DOUT)") (class "Default")
      (node (ref "16") (pin "2") (pinfunction "DOUT_2") (pintype "unspecified"))
      (node (ref "17") (pin "4") (pinfunction "DIN_4") (pintype "unspecified"))
    )
    (net (code "20") (name "Net-(17-DOUT)") (class "Default")
      (node (ref "17") (pin "2") (pinfunction "DOUT_2") (pintype "unspecified"))
      (node (ref "18") (pin "4") (pinfunction "DIN_4") (pintype "unspecified"))
    )
    (net (code "21") (name "Net-(18-DOUT)") (class "Default")
      (node (ref "18") (pin "2") (pinfunction "DOUT_2") (pintype "unspecified"))
      (node (ref "19") (pin "4") (pinfunction "DIN_4") (pintype "unspecified"))
    )
    (net (code "22") (name "Net-(19-DOUT)") (class "Default")
      (node (ref "19") (pin "2") (pinfunction "DOUT_2") (pintype "unspecified"))
      (node (ref "20") (pin "4") (pinfunction "DIN_4") (pintype "unspecified"))
    )
    (net (code "23") (name "Net-(20-DOUT)") (class "Default")
      (node (ref "20") (pin "2") (pinfunction "DOUT_2") (pintype "unspecified"))
      (node (ref "21") (pin "4") (pinfunction "DIN_4") (pintype "unspecified"))
    )
    (net (code "24") (name "Net-(21-DOUT)") (class "Default")
      (node (ref "21") (pin "2") (pinfunction "DOUT_2") (pintype "unspecified"))
      (node (ref "22") (pin "4") (pinfunction "DIN_4") (pintype "unspecified"))
    )
    (net (code "25") (name "Net-(22-DOUT)") (class "Default")
      (node (ref "22") (pin "2") (pinfunction "DOUT_2") (pintype "unspecified"))
      (node (ref "23") (pin "4") (pinfunction "DIN_4") (pintype "unspecified"))
    )
    (net (code "26") (name "Net-(23-DOUT)") (class "Default")
      (node (ref "23") (pin "2") (pinfunction "DOUT_2") (pintype "unspecified"))
      (node (ref "24") (pin "4") (pinfunction "DIN_4") (pintype "unspecified"))
    )
    (net (code "27") (name "Net-(24-DOUT)") (class "Default")
      (node (ref "24") (pin "2") (pinfunction "DOUT_2") (pintype "unspecified"))
      (node (ref "25") (pin "4") (pinfunction "DIN_4") (pintype "unspecified"))
    )
    (net (code "28") (name "Net-(25-DOUT)") (class "Default")
      (node (ref "25") (pin "2") (pinfunction "DOUT_2") (pintype "unspecified"))
      (node (ref "26") (pin "4") (pinfunction "DIN_4") (pintype "unspecified"))
    )
    (net (code "29") (name "Net-(26-DOUT)") (class "Default")
      (node (ref "26") (pin "2") (pinfunction "DOUT_2") (pintype "unspecified"))
      (node (ref "27") (pin "4") (pinfunction "DIN_4") (pintype "unspecified"))
    )
    (net (code "30") (name "Net-(27-DOUT)") (class "Default")
      (node (ref "27") (pin "2") (pinfunction "DOUT_2") (pintype "unspecified"))
      (node (ref "28") (pin "4") (pinfunction "DIN_4") (pintype "unspecified"))
    )
    (net (code "31") (name "Net-(28-DOUT)") (class "Default")
      (node (ref "28") (pin "2") (pinfunction "DOUT_2") (pintype "unspecified"))
      (node (ref "29") (pin "4") (pinfunction "DIN_4") (pintype "unspecified"))
    )
    (net (code "32") (name "Net-(29-DOUT)") (class "Default")
      (node (ref "29") (pin "2") (pinfunction "DOUT_2") (pintype "unspecified"))
      (node (ref "30") (pin "4") (pinfunction "DIN_4") (pintype "unspecified"))
    )
    (net (code "33") (name "Net-(30-DOUT)") (class "Default")
      (node (ref "30") (pin "2") (pinfunction "DOUT_2") (pintype "unspecified"))
      (node (ref "31") (pin "4") (pinfunction "DIN_4") (pintype "unspecified"))
    )
    (net (code "34") (name "Net-(31-DOUT)") (class "Default")
      (node (ref "31") (pin "2") (pinfunction "DOUT_2") (pintype "unspecified"))
      (node (ref "32") (pin "4") (pinfunction "DIN_4") (pintype "unspecified"))
    )
    (net (code "35") (name "Net-(32-DOUT)") (class "Default")
      (node (ref "32") (pin "2") (pinfunction "DOUT_2") (pintype "unspecified"))
      (node (ref "33") (pin "4") (pinfunction "DIN_4") (pintype "unspecified"))
    )
    (net (code "36") (name "Net-(33-DOUT)") (class "Default")
      (node (ref "33") (pin "2") (pinfunction "DOUT_2") (pintype "unspecified"))
      (node (ref "34") (pin "4") (pinfunction "DIN_4") (pintype "unspecified"))
    )
    (net (code "37") (name "Net-(34-DOUT)") (class "Default")
      (node (ref "34") (pin "2") (pinfunction "DOUT_2") (pintype "unspecified"))
      (node (ref "35") (pin "4") (pinfunction "DIN_4") (pintype "unspecified"))
    )
    (net (code "38") (name "Net-(35-DOUT)") (class "Default")
      (node (ref "35") (pin "2") (pinfunction "DOUT_2") (pintype "unspecified"))
      (node (ref "36") (pin "4") (pinfunction "DIN_4") (pintype "unspecified"))
    )
    (net (code "39") (name "Net-(36-DOUT)") (class "Default")
      (node (ref "36") (pin "2") (pinfunction "DOUT_2") (pintype "unspecified"))
      (node (ref "37") (pin "4") (pinfunction "DIN_4") (pintype "unspecified"))
    )
    (net (code "40") (name "Net-(37-DOUT)") (class "Default")
      (node (ref "37") (pin "2") (pinfunction "DOUT_2") (pintype "unspecified"))
      (node (ref "38") (pin "4") (pinfunction "DIN_4") (pintype "unspecified"))
    )
    (net (code "41") (name "Net-(38-DOUT)") (class "Default")
      (node (ref "38") (pin "2") (pinfunction "DOUT_2") (pintype "unspecified"))
      (node (ref "39") (pin "4") (pinfunction "DIN_4") (pintype "unspecified"))
    )
    (net (code "42") (name "Net-(39-DOUT)") (class "Default")
      (node (ref "39") (pin "2") (pinfunction "DOUT_2") (pintype "unspecified"))
      (node (ref "40") (pin "4") (pinfunction "DIN_4") (pintype "unspecified"))
    )
    (net (code "43") (name "Net-(40-DOUT)") (class "Default")
      (node (ref "40") (pin "2") (pinfunction "DOUT_2") (pintype "unspecified"))
      (node (ref "41") (pin "4") (pinfunction "DIN_4") (pintype "unspecified"))
    )
    (net (code "44") (name "Net-(41-DOUT)") (class "Default")
      (node (ref "41") (pin "2") (pinfunction "DOUT_2") (pintype "unspecified"))
      (node (ref "42") (pin "4") (pinfunction "DIN_4") (pintype "unspecified"))
    )
    (net (code "45") (name "Net-(42-DOUT)") (class "Default")
      (node (ref "42") (pin "2") (pinfunction "DOUT_2") (pintype "unspecified"))
      (node (ref "43") (pin "4") (pinfunction "DIN_4") (pintype "unspecified"))
    )
    (net (code "46") (name "Net-(43-DOUT)") (class "Default")
      (node (ref "43") (pin "2") (pinfunction "DOUT_2") (pintype "unspecified"))
      (node (ref "44") (pin "4") (pinfunction "DIN_4") (pintype "unspecified"))
    )
    (net (code "47") (name "Net-(44-DOUT)") (class "Default")
      (node (ref "44") (pin "2") (pinfunction "DOUT_2") (pintype "unspecified"))
      (node (ref "45") (pin "4") (pinfunction "DIN_4") (pintype "unspecified"))
    )
    (net (code "48") (name "Net-(45-DOUT)") (class "Default")
      (node (ref "45") (pin "2") (pinfunction "DOUT_2") (pintype "unspecified"))
      (node (ref "46") (pin "4") (pinfunction "DIN_4") (pintype "unspecified"))
    )
    (net (code "49") (name "Net-(46-DOUT)") (class "Default")
      (node (ref "46") (pin "2") (pinfunction "DOUT_2") (pintype "unspecified"))
      (node (ref "47") (pin "4") (pinfunction "DIN_4") (pintype "unspecified"))
    )
    (net (code "50") (name "Net-(47-DOUT)") (class "Default")
      (node (ref "47") (pin "2") (pinfunction "DOUT_2") (pintype "unspecified"))
      (node (ref "48") (pin "4") (pinfunction "DIN_4") (pintype "unspecified"))
    )
    (net (code "51") (name "Net-(48-DOUT)") (class "Default")
      (node (ref "48") (pin "2") (pinfunction "DOUT_2") (pintype "unspecified"))
      (node (ref "49") (pin "4") (pinfunction "DIN_4") (pintype "unspecified"))
    )
    (net (code "52") (name "Net-(49-DOUT)") (class "Default")
      (node (ref "49") (pin "2") (pinfunction "DOUT_2") (pintype "unspecified"))
      (node (ref "50") (pin "4") (pinfunction "DIN_4") (pintype "unspecified"))
    )
    (net (code "53") (name "Net-(50-DOUT)") (class "Default")
      (node (ref "50") (pin "2") (pinfunction "DOUT_2") (pintype "unspecified"))
      (node (ref "51") (pin "4") (pinfunction "DIN_4") (pintype "unspecified"))
    )
    (net (code "54") (name "Net-(51-DOUT)") (class "Default")
      (node (ref "51") (pin "2") (pinfunction "DOUT_2") (pintype "unspecified"))
      (node (ref "52") (pin "4") (pinfunction "DIN_4") (pintype "unspecified"))
    )
    (net (code "55") (name "Net-(52-DOUT)") (class "Default")
      (node (ref "52") (pin "2") (pinfunction "DOUT_2") (pintype "unspecified"))
      (node (ref "53") (pin "4") (pinfunction "DIN_4") (pintype "unspecified"))
    )
    (net (code "56") (name "Net-(53-DOUT)") (class "Default")
      (node (ref "53") (pin "2") (pinfunction "DOUT_2") (pintype "unspecified"))
      (node (ref "54") (pin "4") (pinfunction "DIN_4") (pintype "unspecified"))
    )
    (net (code "57") (name "Net-(54-DOUT)") (class "Default")
      (node (ref "54") (pin "2") (pinfunction "DOUT_2") (pintype "unspecified"))
      (node (ref "55") (pin "4") (pinfunction "DIN_4") (pintype "unspecified"))
    )
    (net (code "58") (name "Net-(55-DOUT)") (class "Default")
      (node (ref "55") (pin "2") (pinfunction "DOUT_2") (pintype "unspecified"))
      (node (ref "56") (pin "4") (pinfunction "DIN_4") (pintype "unspecified"))
    )
    (net (code "59") (name "Net-(56-DOUT)") (class "Default")
      (node (ref "56") (pin "2") (pinfunction "DOUT_2") (pintype "unspecified"))
      (node (ref "57") (pin "4") (pinfunction "DIN_4") (pintype "unspecified"))
    )
    (net (code "60") (name "Net-(57-DOUT)") (class "Default")
      (node (ref "57") (pin "2") (pinfunction "DOUT_2") (pintype "unspecified"))
      (node (ref "58") (pin "4") (pinfunction "DIN_4") (pintype "unspecified"))
    )
    (net (code "61") (name "Net-(58-DOUT)") (class "Default")
      (node (ref "58") (pin "2") (pinfunction "DOUT_2") (pintype "unspecified"))
      (node (ref "59") (pin "4") (pinfunction "DIN_4") (pintype "unspecified"))
    )
    (net (code "62") (name "Net-(59-DOUT)") (class "Default")
      (node (ref "59") (pin "2") (pinfunction "DOUT_2") (pintype "unspecified"))
      (node (ref "60") (pin "4") (pinfunction "DIN_4") (pintype "unspecified"))
    )
    (net (code "63") (name "Net-(60-DOUT)") (class "Default")
      (node (ref "60") (pin "2") (pinfunction "DOUT_2") (pintype "unspecified"))
      (node (ref "61") (pin "4") (pinfunction "DIN_4") (pintype "unspecified"))
    )
    (net (code "64") (name "Net-(61-DOUT)") (class "Default")
      (node (ref "61") (pin "2") (pinfunction "DOUT_2") (pintype "unspecified"))
      (node (ref "62") (pin "4") (pinfunction "DIN_4") (pintype "unspecified"))
    )
    (net (code "65") (name "Net-(62-DOUT)") (class "Default")
      (node (ref "62") (pin "2") (pinfunction "DOUT_2") (pintype "unspecified"))
      (node (ref "63") (pin "4") (pinfunction "DIN_4") (pintype "unspecified"))
    )
    (net (code "66") (name "Net-(63-DOUT)") (class "Default")
      (node (ref "63") (pin "2") (pinfunction "DOUT_2") (pintype "unspecified"))
      (node (ref "64") (pin "4") (pinfunction "DIN_4") (pintype "unspecified"))
    )
    (net (code "67") (name "Net-(64-DOUT)") (class "Default")
      (node (ref "64") (pin "2") (pinfunction "DOUT_2") (pintype "unspecified"))
      (node (ref "65") (pin "4") (pinfunction "DIN_4") (pintype "unspecified"))
    )
    (net (code "68") (name "Net-(65-DOUT)") (class "Default")
      (node (ref "65") (pin "2") (pinfunction "DOUT_2") (pintype "unspecified"))
      (node (ref "66") (pin "4") (pinfunction "DIN_4") (pintype "unspecified"))
    )
    (net (code "69") (name "Net-(66-DOUT)") (class "Default")
      (node (ref "66") (pin "2") (pinfunction "DOUT_2") (pintype "unspecified"))
      (node (ref "67") (pin "4") (pinfunction "DIN_4") (pintype "unspecified"))
    )
    (net (code "70") (name "Net-(67-DOUT)") (class "Default")
      (node (ref "67") (pin "2") (pinfunction "DOUT_2") (pintype "unspecified"))
      (node (ref "68") (pin "4") (pinfunction "DIN_4") (pintype "unspecified"))
    )
    (net (code "71") (name "Net-(68-DOUT)") (class "Default")
      (node (ref "68") (pin "2") (pinfunction "DOUT_2") (pintype "unspecified"))
      (node (ref "69") (pin "4") (pinfunction "DIN_4") (pintype "unspecified"))
    )
    (net (code "72") (name "Net-(69-DOUT)") (class "Default")
      (node (ref "69") (pin "2") (pinfunction "DOUT_2") (pintype "unspecified"))
      (node (ref "70") (pin "4") (pinfunction "DIN_4") (pintype "unspecified"))
    )
    (net (code "73") (name "Net-(70-DOUT)") (class "Default")
      (node (ref "70") (pin "2") (pinfunction "DOUT_2") (pintype "unspecified"))
      (node (ref "71") (pin "4") (pinfunction "DIN_4") (pintype "unspecified"))
    )
    (net (code "74") (name "Net-(71-DOUT)") (class "Default")
      (node (ref "71") (pin "2") (pinfunction "DOUT_2") (pintype "unspecified"))
      (node (ref "72") (pin "4") (pinfunction "DIN_4") (pintype "unspecified"))
    )
    (net (code "75") (name "Net-(72-DOUT)") (class "Default")
      (node (ref "72") (pin "2") (pinfunction "DOUT_2") (pintype "unspecified"))
      (node (ref "73") (pin "4") (pinfunction "DIN_4") (pintype "unspecified"))
    )
    (net (code "76") (name "Net-(73-DOUT)") (class "Default")
      (node (ref "73") (pin "2") (pinfunction "DOUT_2") (pintype "unspecified"))
      (node (ref "74") (pin "4") (pinfunction "DIN_4") (pintype "unspecified"))
    )
    (net (code "77") (name "Net-(74-DOUT)") (class "Default")
      (node (ref "74") (pin "2") (pinfunction "DOUT_2") (pintype "unspecified"))
      (node (ref "75") (pin "4") (pinfunction "DIN_4") (pintype "unspecified"))
    )
    (net (code "78") (name "Net-(75-DOUT)") (class "Default")
      (node (ref "75") (pin "2") (pinfunction "DOUT_2") (pintype "unspecified"))
      (node (ref "76") (pin "4") (pinfunction "DIN_4") (pintype "unspecified"))
    )
    (net (code "79") (name "Net-(76-DOUT)") (class "Default")
      (node (ref "76") (pin "2") (pinfunction "DOUT_2") (pintype "unspecified"))
      (node (ref "77") (pin "4") (pinfunction "DIN_4") (pintype "unspecified"))
    )
    (net (code "80") (name "Net-(77-DOUT)") (class "Default")
      (node (ref "77") (pin "2") (pinfunction "DOUT_2") (pintype "unspecified"))
      (node (ref "78") (pin "4") (pinfunction "DIN_4") (pintype "unspecified"))
    )
    (net (code "81") (name "Net-(78-DOUT)") (class "Default")
      (node (ref "78") (pin "2") (pinfunction "DOUT_2") (pintype "unspecified"))
      (node (ref "79") (pin "4") (pinfunction "DIN_4") (pintype "unspecified"))
    )
    (net (code "82") (name "Net-(79-DOUT)") (class "Default")
      (node (ref "79") (pin "2") (pinfunction "DOUT_2") (pintype "unspecified"))
      (node (ref "80") (pin "4") (pinfunction "DIN_4") (pintype "unspecified"))
    )
    (net (code "83") (name "Net-(80-DOUT)") (class "Default")
      (node (ref "80") (pin "2") (pinfunction "DOUT_2") (pintype "unspecified"))
      (node (ref "81") (pin "4") (pinfunction "DIN_4") (pintype "unspecified"))
    )
    (net (code "84") (name "Net-(81-DOUT)") (class "Default")
      (node (ref "81") (pin "2") (pinfunction "DOUT_2") (pintype "unspecified"))
      (node (ref "82") (pin "4") (pinfunction "DIN_4") (pintype "unspecified"))
    )
    (net (code "85") (name "Net-(82-DOUT)") (class "Default")
      (node (ref "82") (pin "2") (pinfunction "DOUT_2") (pintype "unspecified"))
      (node (ref "83") (pin "4") (pinfunction "DIN_4") (pintype "unspecified"))
    )
    (net (code "86") (name "Net-(83-DOUT)") (class "Default")
      (node (ref "83") (pin "2") (pinfunction "DOUT_2") (pintype "unspecified"))
      (node (ref "84") (pin "4") (pinfunction "DIN_4") (pintype "unspecified"))
    )
    (net (code "87") (name "Net-(84-DOUT)") (class "Default")
      (node (ref "84") (pin "2") (pinfunction "DOUT_2") (pintype "unspecified"))
      (node (ref "85") (pin "4") (pinfunction "DIN_4") (pintype "unspecified"))
    )
    (net (code "88") (name "Net-(85-DOUT)") (class "Default")
      (node (ref "85") (pin "2") (pinfunction "DOUT_2") (pintype "unspecified"))
      (node (ref "86") (pin "4") (pinfunction "DIN_4") (pintype "unspecified"))
    )
    (net (code "89") (name "Net-(86-DOUT)") (class "Default")
      (node (ref "86") (pin "2") (pinfunction "DOUT_2") (pintype "unspecified"))
      (node (ref "87") (pin "4") (pinfunction "DIN_4") (pintype "unspecified"))
    )
    (net (code "90") (name "Net-(87-DOUT)") (class "Default")
      (node (ref "87") (pin "2") (pinfunction "DOUT_2") (pintype "unspecified"))
      (node (ref "88") (pin "4") (pinfunction "DIN_4") (pintype "unspecified"))
    )
    (net (code "91") (name "Net-(88-DOUT)") (class "Default")
      (node (ref "88") (pin "2") (pinfunction "DOUT_2") (pintype "unspecified"))
      (node (ref "89") (pin "4") (pinfunction "DIN_4") (pintype "unspecified"))
    )
    (net (code "92") (name "Net-(89-DOUT)") (class "Default")
      (node (ref "89") (pin "2") (pinfunction "DOUT_2") (pintype "unspecified"))
      (node (ref "90") (pin "4") (pinfunction "DIN_4") (pintype "unspecified"))
    )
    (net (code "93") (name "Net-(90-DOUT)") (class "Default")
      (node (ref "90") (pin "2") (pinfunction "DOUT_2") (pintype "unspecified"))
      (node (ref "91") (pin "4") (pinfunction "DIN_4") (pintype "unspecified"))
    )
    (net (code "94") (name "Net-(91-DOUT)") (class "Default")
      (node (ref "91") (pin "2") (pinfunction "DOUT_2") (pintype "unspecified"))
      (node (ref "92") (pin "4") (pinfunction "DIN_4") (pintype "unspecified"))
    )
    (net (code "95") (name "Net-(92-DOUT)") (class "Default")
      (node (ref "92") (pin "2") (pinfunction "DOUT_2") (pintype "unspecified"))
      (node (ref "93") (pin "4") (pinfunction "DIN_4") (pintype "unspecified"))
    )
    (net (code "96") (name "Net-(93-DOUT)") (class "Default")
      (node (ref "93") (pin "2") (pinfunction "DOUT_2") (pintype "unspecified"))
      (node (ref "94") (pin "4") (pinfunction "DIN_4") (pintype "unspecified"))
    )
    (net (code "97") (name "Net-(94-DOUT)") (class "Default")
      (node (ref "94") (pin "2") (pinfunction "DOUT_2") (pintype "unspecified"))
      (node (ref "95") (pin "4") (pinfunction "DIN_4") (pintype "unspecified"))
    )
    (net (code "98") (name "Net-(95-DOUT)") (class "Default")
      (node (ref "95") (pin "2") (pinfunction "DOUT_2") (pintype "unspecified"))
      (node (ref "96") (pin "4") (pinfunction "DIN_4") (pintype "unspecified"))
    )
    (net (code "99") (name "Net-(96-DOUT)") (class "Default")
      (node (ref "96") (pin "2") (pinfunction "DOUT_2") (pintype "unspecified"))
      (node (ref "97") (pin "4") (pinfunction "DIN_4") (pintype "unspecified"))
    )
    (net (code "100") (name "Net-(97-DOUT)") (class "Default")
      (node (ref "97") (pin "2") (pinfunction "DOUT_2") (pintype "unspecified"))
      (node (ref "98") (pin "4") (pinfunction "DIN_4") (pintype "unspecified"))
    )
    (net (code "101") (name "Net-(98-DOUT)") (class "Default")
      (node (ref "98") (pin "2") (pinfunction "DOUT_2") (pintype "unspecified"))
      (node (ref "99") (pin "4") (pinfunction "DIN_4") (pintype "unspecified"))
    )
    (net (code "102") (name "Net-(100-DIN)") (class "Default")
      (node (ref "100") (pin "4") (pinfunction "DIN_4") (pintype "unspecified"))
      (node (ref "99") (pin "2") (pinfunction "DOUT_2") (pintype "unspecified"))
    )
    (net (code "103") (name "unconnected-(100-DOUT-Pad2)") (class "Default")
      (node (ref "100") (pin "2") (pinfunction "DOUT_2") (pintype "unspecified"))
    )
  )
)
